# Debugger.net
KiCad netlist of a schematic drawn in Altium Designer
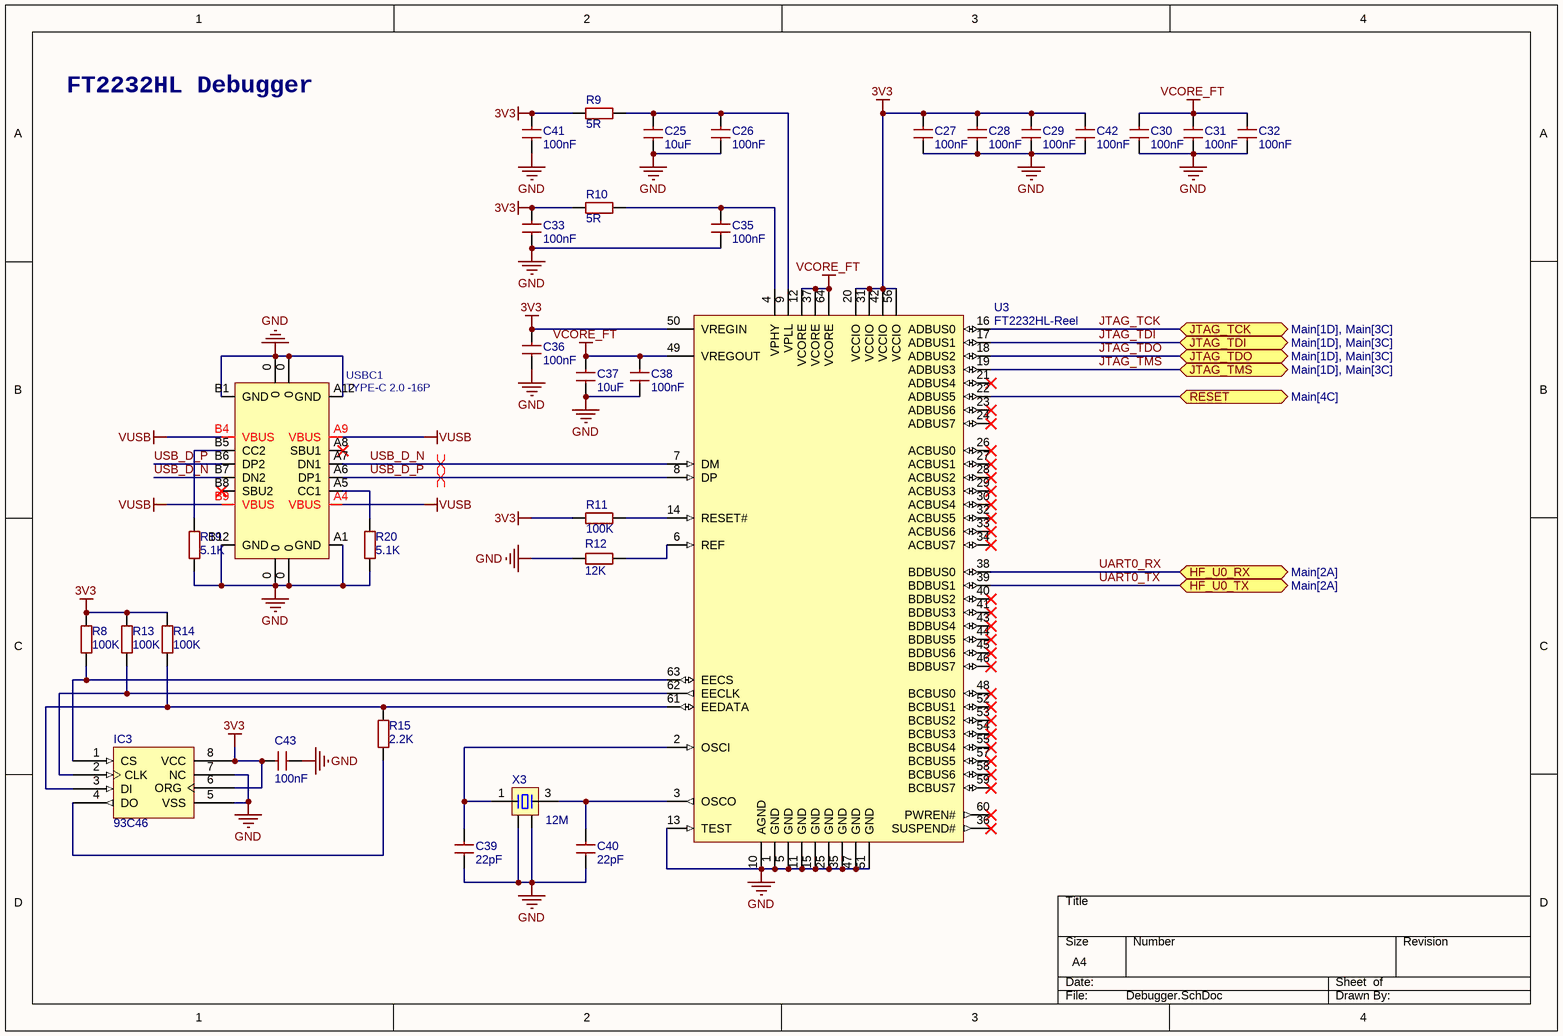
[diagram p0: Debugger.SchDoc]

(export (version "E")
  (design (tool "Eeschema 10.0.6"))
  (components
    (comp (ref "C25")
      (value "10uF")
      (footprint "C0603_NS")
      (description "贴片电容/MLCC电容")
      (libsource (lib "0.1 - 电阻-电容-电感-晶振-晶体-磁珠-电位器-法拉电容-馈通电容") (part "C"))
    )
    (comp (ref "C26")
      (value "100nF")
      (footprint "C0603_NS")
      (description "贴片电容/MLCC电容")
      (libsource (lib "0.1 - 电阻-电容-电感-晶振-晶体-磁珠-电位器-法拉电容-馈通电容") (part "C"))
    )
    (comp (ref "C27")
      (value "100nF")
      (footprint "C0603_NS")
      (description "贴片电容/MLCC电容")
      (libsource (lib "0.1 - 电阻-电容-电感-晶振-晶体-磁珠-电位器-法拉电容-馈通电容") (part "C"))
    )
    (comp (ref "C28")
      (value "100nF")
      (footprint "C0603_NS")
      (description "贴片电容/MLCC电容")
      (libsource (lib "0.1 - 电阻-电容-电感-晶振-晶体-磁珠-电位器-法拉电容-馈通电容") (part "C"))
    )
    (comp (ref "C29")
      (value "100nF")
      (footprint "C0603_NS")
      (description "贴片电容/MLCC电容")
      (libsource (lib "0.1 - 电阻-电容-电感-晶振-晶体-磁珠-电位器-法拉电容-馈通电容") (part "C"))
    )
    (comp (ref "C30")
      (value "100nF")
      (footprint "C0603_NS")
      (description "贴片电容/MLCC电容")
      (libsource (lib "0.1 - 电阻-电容-电感-晶振-晶体-磁珠-电位器-法拉电容-馈通电容") (part "C"))
    )
    (comp (ref "C31")
      (value "100nF")
      (footprint "C0603_NS")
      (description "贴片电容/MLCC电容")
      (libsource (lib "0.1 - 电阻-电容-电感-晶振-晶体-磁珠-电位器-法拉电容-馈通电容") (part "C"))
    )
    (comp (ref "C32")
      (value "100nF")
      (footprint "C0603_NS")
      (description "贴片电容/MLCC电容")
      (libsource (lib "0.1 - 电阻-电容-电感-晶振-晶体-磁珠-电位器-法拉电容-馈通电容") (part "C"))
    )
    (comp (ref "C33")
      (value "100nF")
      (footprint "C0603_NS")
      (description "贴片电容/MLCC电容")
      (libsource (lib "0.1 - 电阻-电容-电感-晶振-晶体-磁珠-电位器-法拉电容-馈通电容") (part "C"))
    )
    (comp (ref "C35")
      (value "100nF")
      (footprint "C0603_NS")
      (description "贴片电容/MLCC电容")
      (libsource (lib "0.1 - 电阻-电容-电感-晶振-晶体-磁珠-电位器-法拉电容-馈通电容") (part "C"))
    )
    (comp (ref "C36")
      (value "100nF")
      (footprint "C0603_NS")
      (description "贴片电容/MLCC电容")
      (libsource (lib "0.1 - 电阻-电容-电感-晶振-晶体-磁珠-电位器-法拉电容-馈通电容") (part "C"))
    )
    (comp (ref "C37")
      (value "10uF")
      (footprint "C0603_NS")
      (description "贴片电容/MLCC电容")
      (libsource (lib "0.1 - 电阻-电容-电感-晶振-晶体-磁珠-电位器-法拉电容-馈通电容") (part "C"))
    )
    (comp (ref "C38")
      (value "100nF")
      (footprint "C0603_NS")
      (description "贴片电容/MLCC电容")
      (libsource (lib "0.1 - 电阻-电容-电感-晶振-晶体-磁珠-电位器-法拉电容-馈通电容") (part "C"))
    )
    (comp (ref "C39")
      (value "22pF")
      (footprint "C0603_NS")
      (description "贴片电容/MLCC电容")
      (libsource (lib "0.1 - 电阻-电容-电感-晶振-晶体-磁珠-电位器-法拉电容-馈通电容") (part "C"))
    )
    (comp (ref "C40")
      (value "22pF")
      (footprint "C0603_NS")
      (description "贴片电容/MLCC电容")
      (libsource (lib "0.1 - 电阻-电容-电感-晶振-晶体-磁珠-电位器-法拉电容-馈通电容") (part "C"))
    )
    (comp (ref "C41")
      (value "100nF")
      (footprint "C0603_NS")
      (description "贴片电容/MLCC电容")
      (libsource (lib "0.1 - 电阻-电容-电感-晶振-晶体-磁珠-电位器-法拉电容-馈通电容") (part "C"))
    )
    (comp (ref "C42")
      (value "100nF")
      (footprint "C0603_NS")
      (description "贴片电容/MLCC电容")
      (libsource (lib "0.1 - 电阻-电容-电感-晶振-晶体-磁珠-电位器-法拉电容-馈通电容") (part "C"))
    )
    (comp (ref "C43")
      (value "100nF")
      (footprint "C0603_NS")
      (description "贴片电容/MLCC电容")
      (libsource (lib "0.1 - 电阻-电容-电感-晶振-晶体-磁珠-电位器-法拉电容-馈通电容") (part "C"))
    )
    (comp (ref "IC3")
      (value "93C46")
      (footprint "SOP8_L")
      (description "外置EEPROM")
      (libsource (lib "0.8 - 常见芯片") (part "93C46"))
    )
    (comp (ref "R8")
      (value "100K")
      (footprint "R0603_NS")
      (description "贴片电阻")
      (libsource (lib "0.1 - 电阻-电容-电感-晶振-晶体-磁珠-电位器-法拉电容-馈通电容") (part "R"))
    )
    (comp (ref "R9")
      (value "5R")
      (footprint "R0603_NS")
      (description "贴片电阻")
      (libsource (lib "") (part "R_2"))
    )
    (comp (ref "R10")
      (value "5R")
      (footprint "R0603_NS")
      (description "贴片电阻")
      (libsource (lib "") (part "R_2"))
    )
    (comp (ref "R11")
      (value "100K")
      (footprint "R0603_NS")
      (description "贴片电阻")
      (libsource (lib "") (part "R_2"))
    )
    (comp (ref "R12")
      (value "12K")
      (footprint "R0603_NS")
      (description "贴片电阻")
      (libsource (lib "") (part "R_3"))
    )
    (comp (ref "R13")
      (value "100K")
      (footprint "R0603_NS")
      (description "贴片电阻")
      (libsource (lib "0.1 - 电阻-电容-电感-晶振-晶体-磁珠-电位器-法拉电容-馈通电容") (part "R"))
    )
    (comp (ref "R14")
      (value "100K")
      (footprint "R0603_NS")
      (description "贴片电阻")
      (libsource (lib "0.1 - 电阻-电容-电感-晶振-晶体-磁珠-电位器-法拉电容-馈通电容") (part "R"))
    )
    (comp (ref "R15")
      (value "2.2K")
      (footprint "R0603_NS")
      (description "贴片电阻")
      (libsource (lib "") (part "R_1"))
    )
    (comp (ref "R19")
      (value "5.1K")
      (footprint "R0603_NS")
      (description "贴片电阻")
      (libsource (lib "0.1 - 电阻-电容-电感-晶振-晶体-磁珠-电位器-法拉电容-馈通电容") (part "R"))
    )
    (comp (ref "R20")
      (value "5.1K")
      (footprint "R0603_NS")
      (description "贴片电阻")
      (libsource (lib "0.1 - 电阻-电容-电感-晶振-晶体-磁珠-电位器-法拉电容-馈通电容") (part "R"))
    )
    (comp (ref "U3")
      (value "FT2232HL-Reel")
      (footprint "LQFP-64_M")
      (description "Dual High Speed USB To Multipurpose UART/FIFO IC, 64-pin LQFP, Tape and Reel")
      (fields (field (name "MANUFACTURER") "FTDI"))
      (libsource (lib "Altium Content Vault") (part "COM-UART-FT2232H-LQFP64"))
    )
    (comp (ref "USBC1")
      (value "TYPE-C 2.0 -16P")
      (footprint "USB-C-SMD_16P")
      (description "USB2.0_Type-C_16Pin母座")
      (libsource (lib "0.6 - 电源_RJ45以太网_音频_SD-TF_SIM_ USB Type-C_HDMI插座") (part "USB2.0_Type-C_16Pin"))
    )
    (comp (ref "X3")
      (value "12M")
      (footprint "XTAL-2025-4P")
      (description "4脚无源晶振(谐振器）")
      (libsource (lib "0.1 - 电阻-电容-电感-晶振-晶体-磁珠-电位器-法拉电容-馈通电容") (part "XTAL-4P"))
    )
  )
  (nets
    (net (code "1") (name "/JTAG_TCK") (class "Default")
      (node (ref "U3") (pin "16") (pinfunction "ADBUS0_16") (pintype "bidirectional"))
    )
    (net (code "2") (name "/JTAG_TDI") (class "Default")
      (node (ref "U3") (pin "17") (pinfunction "ADBUS1_17") (pintype "bidirectional"))
    )
    (net (code "3") (name "/JTAG_TDO") (class "Default")
      (node (ref "U3") (pin "18") (pinfunction "ADBUS2_18") (pintype "bidirectional"))
    )
    (net (code "4") (name "/JTAG_TMS") (class "Default")
      (node (ref "U3") (pin "19") (pinfunction "ADBUS3_19") (pintype "bidirectional"))
    )
    (net (code "5") (name "/RESET") (class "Default")
      (node (ref "U3") (pin "22") (pinfunction "ADBUS5_22") (pintype "bidirectional"))
    )
    (net (code "6") (name "/UART0_RX") (class "Default")
      (node (ref "U3") (pin "38") (pinfunction "BDBUS0_38") (pintype "bidirectional"))
    )
    (net (code "7") (name "/UART0_TX") (class "Default")
      (node (ref "U3") (pin "39") (pinfunction "BDBUS1_39") (pintype "bidirectional"))
    )
    (net (code "8") (name "/USB_D_N") (class "Default")
      (node (ref "U3") (pin "7") (pinfunction "DM_7") (pintype "input"))
      (node (ref "USBC1") (pin "A7") (pinfunction "DN1_A7") (pintype "passive"))
      (node (ref "USBC1") (pin "B7") (pinfunction "DN2_B7") (pintype "passive"))
    )
    (net (code "9") (name "/USB_D_P") (class "Default")
      (node (ref "U3") (pin "8") (pinfunction "DP_8") (pintype "input"))
      (node (ref "USBC1") (pin "A6") (pinfunction "DP1_A6") (pintype "passive"))
      (node (ref "USBC1") (pin "B6") (pinfunction "DP2_B6") (pintype "passive"))
    )
    (net (code "10") (name "3V3") (class "Default")
      (node (ref "C27") (pin "2") (pinfunction "2_2") (pintype "passive"))
      (node (ref "C28") (pin "2") (pinfunction "2_2") (pintype "passive"))
      (node (ref "C29") (pin "2") (pinfunction "2_2") (pintype "passive"))
      (node (ref "C33") (pin "2") (pinfunction "2_2") (pintype "passive"))
      (node (ref "C36") (pin "2") (pinfunction "2_2") (pintype "passive"))
      (node (ref "C41") (pin "2") (pinfunction "2_2") (pintype "passive"))
      (node (ref "C42") (pin "2") (pinfunction "2_2") (pintype "passive"))
      (node (ref "C43") (pin "1") (pinfunction "1_1") (pintype "passive"))
      (node (ref "IC3") (pin "6") (pinfunction "ORG_6") (pintype "passive"))
      (node (ref "IC3") (pin "8") (pinfunction "VCC_8") (pintype "power_in"))
      (node (ref "R10") (pin "2") (pinfunction "2_2") (pintype "passive"))
      (node (ref "R11") (pin "2") (pinfunction "2_2") (pintype "passive"))
      (node (ref "R13") (pin "2") (pinfunction "2_2") (pintype "passive"))
      (node (ref "R14") (pin "2") (pinfunction "2_2") (pintype "passive"))
      (node (ref "R8") (pin "2") (pinfunction "2_2") (pintype "passive"))
      (node (ref "R9") (pin "2") (pinfunction "2_2") (pintype "passive"))
      (node (ref "U3") (pin "20") (pinfunction "VCCIO_20") (pintype "power_in"))
      (node (ref "U3") (pin "31") (pinfunction "VCCIO_31") (pintype "power_in"))
      (node (ref "U3") (pin "42") (pinfunction "VCCIO_42") (pintype "power_in"))
      (node (ref "U3") (pin "50") (pinfunction "VREGIN_50") (pintype "power_in"))
      (node (ref "U3") (pin "56") (pinfunction "VCCIO_56") (pintype "power_in"))
    )
    (net (code "11") (name "GND") (class "Default")
      (node (ref "C25") (pin "1") (pinfunction "1_1") (pintype "passive"))
      (node (ref "C26") (pin "1") (pinfunction "1_1") (pintype "passive"))
      (node (ref "C27") (pin "1") (pinfunction "1_1") (pintype "passive"))
      (node (ref "C28") (pin "1") (pinfunction "1_1") (pintype "passive"))
      (node (ref "C29") (pin "1") (pinfunction "1_1") (pintype "passive"))
      (node (ref "C30") (pin "1") (pinfunction "1_1") (pintype "passive"))
      (node (ref "C31") (pin "1") (pinfunction "1_1") (pintype "passive"))
      (node (ref "C32") (pin "1") (pinfunction "1_1") (pintype "passive"))
      (node (ref "C33") (pin "1") (pinfunction "1_1") (pintype "passive"))
      (node (ref "C35") (pin "1") (pinfunction "1_1") (pintype "passive"))
      (node (ref "C36") (pin "1") (pinfunction "1_1") (pintype "passive"))
      (node (ref "C37") (pin "1") (pinfunction "1_1") (pintype "passive"))
      (node (ref "C38") (pin "1") (pinfunction "1_1") (pintype "passive"))
      (node (ref "C39") (pin "1") (pinfunction "1_1") (pintype "passive"))
      (node (ref "C40") (pin "1") (pinfunction "1_1") (pintype "passive"))
      (node (ref "C41") (pin "1") (pinfunction "1_1") (pintype "passive"))
      (node (ref "C42") (pin "1") (pinfunction "1_1") (pintype "passive"))
      (node (ref "C43") (pin "2") (pinfunction "2_2") (pintype "passive"))
      (node (ref "IC3") (pin "5") (pinfunction "VSS_5") (pintype "passive"))
      (node (ref "IC3") (pin "7") (pinfunction "NC_7") (pintype "passive"))
      (node (ref "R12") (pin "1") (pinfunction "1_1") (pintype "passive"))
      (node (ref "R19") (pin "1") (pinfunction "1_1") (pintype "passive"))
      (node (ref "R20") (pin "1") (pinfunction "1_1") (pintype "passive"))
      (node (ref "U3") (pin "1") (pinfunction "GND_1") (pintype "power_in"))
      (node (ref "U3") (pin "10") (pinfunction "AGND_10") (pintype "power_in"))
      (node (ref "U3") (pin "11") (pinfunction "GND_11") (pintype "power_in"))
      (node (ref "U3") (pin "13") (pinfunction "TEST_13") (pintype "input"))
      (node (ref "U3") (pin "15") (pinfunction "GND_15") (pintype "power_in"))
      (node (ref "U3") (pin "25") (pinfunction "GND_25") (pintype "power_in"))
      (node (ref "U3") (pin "35") (pinfunction "GND_35") (pintype "power_in"))
      (node (ref "U3") (pin "47") (pinfunction "GND_47") (pintype "power_in"))
      (node (ref "U3") (pin "5") (pinfunction "GND_5") (pintype "power_in"))
      (node (ref "U3") (pin "51") (pinfunction "GND_51") (pintype "power_in"))
      (node (ref "USBC1") (pin "0") (pinfunction "0_0") (pintype "passive"))
      (node (ref "USBC1") (pin "A1") (pinfunction "GND_A1") (pintype "passive"))
      (node (ref "USBC1") (pin "A12") (pinfunction "GND_A12") (pintype "passive"))
      (node (ref "USBC1") (pin "B1") (pinfunction "GND_B1") (pintype "passive"))
      (node (ref "USBC1") (pin "B12") (pinfunction "GND_B12") (pintype "passive"))
      (node (ref "X3") (pin "2") (pinfunction "2_2") (pintype "passive"))
      (node (ref "X3") (pin "4") (pinfunction "4_4") (pintype "passive"))
    )
    (net (code "12") (name "Net-(IC3-CLK)") (class "Default")
      (node (ref "IC3") (pin "2") (pinfunction "CLK_2") (pintype "input"))
      (node (ref "R13") (pin "1") (pinfunction "1_1") (pintype "passive"))
      (node (ref "U3") (pin "62") (pinfunction "EECLK_62") (pintype "output"))
    )
    (net (code "13") (name "Net-(IC3-CS)") (class "Default")
      (node (ref "IC3") (pin "1") (pinfunction "CS_1") (pintype "input"))
      (node (ref "R8") (pin "1") (pinfunction "1_1") (pintype "passive"))
      (node (ref "U3") (pin "63") (pinfunction "EECS_63") (pintype "bidirectional"))
    )
    (net (code "14") (name "Net-(IC3-DI)") (class "Default")
      (node (ref "IC3") (pin "3") (pinfunction "DI_3") (pintype "input"))
      (node (ref "R14") (pin "1") (pinfunction "1_1") (pintype "passive"))
      (node (ref "R15") (pin "1") (pinfunction "1_1") (pintype "passive"))
      (node (ref "U3") (pin "61") (pinfunction "EEDATA_61") (pintype "bidirectional"))
    )
    (net (code "15") (name "Net-(IC3-DO)") (class "Default")
      (node (ref "IC3") (pin "4") (pinfunction "DO_4") (pintype "output"))
      (node (ref "R15") (pin "2") (pinfunction "2_2") (pintype "passive"))
    )
    (net (code "16") (name "Net-(U3-OSCI)") (class "Default")
      (node (ref "C39") (pin "2") (pinfunction "2_2") (pintype "passive"))
      (node (ref "U3") (pin "2") (pinfunction "OSCI_2") (pintype "input"))
      (node (ref "X3") (pin "1") (pinfunction "1_1") (pintype "passive"))
    )
    (net (code "17") (name "Net-(U3-OSCO)") (class "Default")
      (node (ref "C40") (pin "2") (pinfunction "2_2") (pintype "passive"))
      (node (ref "U3") (pin "3") (pinfunction "OSCO_3") (pintype "output"))
      (node (ref "X3") (pin "3") (pinfunction "3_3") (pintype "passive"))
    )
    (net (code "18") (name "Net-(U3-REF)") (class "Default")
      (node (ref "R12") (pin "2") (pinfunction "2_2") (pintype "passive"))
      (node (ref "U3") (pin "6") (pinfunction "REF_6") (pintype "input"))
    )
    (net (code "19") (name "Net-(U3-RESET#)") (class "Default")
      (node (ref "R11") (pin "1") (pinfunction "1_1") (pintype "passive"))
      (node (ref "U3") (pin "14") (pinfunction "RESET#_14") (pintype "input"))
    )
    (net (code "20") (name "Net-(U3-VPHY)") (class "Default")
      (node (ref "C35") (pin "2") (pinfunction "2_2") (pintype "passive"))
      (node (ref "R10") (pin "1") (pinfunction "1_1") (pintype "passive"))
      (node (ref "U3") (pin "4") (pinfunction "VPHY_4") (pintype "power_in"))
    )
    (net (code "21") (name "Net-(U3-VPLL)") (class "Default")
      (node (ref "C25") (pin "2") (pinfunction "2_2") (pintype "passive"))
      (node (ref "C26") (pin "2") (pinfunction "2_2") (pintype "passive"))
      (node (ref "R9") (pin "1") (pinfunction "1_1") (pintype "passive"))
      (node (ref "U3") (pin "9") (pinfunction "VPLL_9") (pintype "power_in"))
    )
    (net (code "22") (name "Net-(USBC1-CC1)") (class "Default")
      (node (ref "R20") (pin "2") (pinfunction "2_2") (pintype "passive"))
      (node (ref "USBC1") (pin "A5") (pinfunction "CC1_A5") (pintype "passive"))
    )
    (net (code "23") (name "Net-(USBC1-CC2)") (class "Default")
      (node (ref "R19") (pin "2") (pinfunction "2_2") (pintype "passive"))
      (node (ref "USBC1") (pin "B5") (pinfunction "CC2_B5") (pintype "passive"))
    )
    (net (code "24") (name "VCORE_FT") (class "Default")
      (node (ref "C30") (pin "2") (pinfunction "2_2") (pintype "passive"))
      (node (ref "C31") (pin "2") (pinfunction "2_2") (pintype "passive"))
      (node (ref "C32") (pin "2") (pinfunction "2_2") (pintype "passive"))
      (node (ref "C37") (pin "2") (pinfunction "2_2") (pintype "passive"))
      (node (ref "C38") (pin "2") (pinfunction "2_2") (pintype "passive"))
      (node (ref "U3") (pin "12") (pinfunction "VCORE_12") (pintype "power_in"))
      (node (ref "U3") (pin "37") (pinfunction "VCORE_37") (pintype "power_in"))
      (node (ref "U3") (pin "49") (pinfunction "VREGOUT_49") (pintype "power_in"))
      (node (ref "U3") (pin "64") (pinfunction "VCORE_64") (pintype "power_in"))
    )
    (net (code "25") (name "VUSB") (class "Default")
      (node (ref "USBC1") (pin "A4") (pinfunction "VBUS_A4") (pintype "passive"))
      (node (ref "USBC1") (pin "A9") (pinfunction "VBUS_A9") (pintype "passive"))
      (node (ref "USBC1") (pin "B4") (pinfunction "VBUS_B4") (pintype "passive"))
      (node (ref "USBC1") (pin "B9") (pinfunction "VBUS_B9") (pintype "passive"))
    )
    (net (code "26") (name "unconnected-(U3-ACBUS0-Pad26)") (class "Default")
      (node (ref "U3") (pin "26") (pinfunction "ACBUS0_26") (pintype "bidirectional+no_connect"))
    )
    (net (code "27") (name "unconnected-(U3-ACBUS1-Pad27)") (class "Default")
      (node (ref "U3") (pin "27") (pinfunction "ACBUS1_27") (pintype "bidirectional+no_connect"))
    )
    (net (code "28") (name "unconnected-(U3-ACBUS2-Pad28)") (class "Default")
      (node (ref "U3") (pin "28") (pinfunction "ACBUS2_28") (pintype "bidirectional+no_connect"))
    )
    (net (code "29") (name "unconnected-(U3-ACBUS3-Pad29)") (class "Default")
      (node (ref "U3") (pin "29") (pinfunction "ACBUS3_29") (pintype "bidirectional+no_connect"))
    )
    (net (code "30") (name "unconnected-(U3-ACBUS4-Pad30)") (class "Default")
      (node (ref "U3") (pin "30") (pinfunction "ACBUS4_30") (pintype "bidirectional+no_connect"))
    )
    (net (code "31") (name "unconnected-(U3-ACBUS5-Pad32)") (class "Default")
      (node (ref "U3") (pin "32") (pinfunction "ACBUS5_32") (pintype "bidirectional+no_connect"))
    )
    (net (code "32") (name "unconnected-(U3-ACBUS6-Pad33)") (class "Default")
      (node (ref "U3") (pin "33") (pinfunction "ACBUS6_33") (pintype "bidirectional+no_connect"))
    )
    (net (code "33") (name "unconnected-(U3-ACBUS7-Pad34)") (class "Default")
      (node (ref "U3") (pin "34") (pinfunction "ACBUS7_34") (pintype "bidirectional+no_connect"))
    )
    (net (code "34") (name "unconnected-(U3-ADBUS4-Pad21)") (class "Default")
      (node (ref "U3") (pin "21") (pinfunction "ADBUS4_21") (pintype "bidirectional+no_connect"))
    )
    (net (code "35") (name "unconnected-(U3-ADBUS6-Pad23)") (class "Default")
      (node (ref "U3") (pin "23") (pinfunction "ADBUS6_23") (pintype "bidirectional+no_connect"))
    )
    (net (code "36") (name "unconnected-(U3-ADBUS7-Pad24)") (class "Default")
      (node (ref "U3") (pin "24") (pinfunction "ADBUS7_24") (pintype "bidirectional+no_connect"))
    )
    (net (code "37") (name "unconnected-(U3-BCBUS0-Pad48)") (class "Default")
      (node (ref "U3") (pin "48") (pinfunction "BCBUS0_48") (pintype "bidirectional+no_connect"))
    )
    (net (code "38") (name "unconnected-(U3-BCBUS1-Pad52)") (class "Default")
      (node (ref "U3") (pin "52") (pinfunction "BCBUS1_52") (pintype "bidirectional+no_connect"))
    )
    (net (code "39") (name "unconnected-(U3-BCBUS2-Pad53)") (class "Default")
      (node (ref "U3") (pin "53") (pinfunction "BCBUS2_53") (pintype "bidirectional+no_connect"))
    )
    (net (code "40") (name "unconnected-(U3-BCBUS3-Pad54)") (class "Default")
      (node (ref "U3") (pin "54") (pinfunction "BCBUS3_54") (pintype "bidirectional+no_connect"))
    )
    (net (code "41") (name "unconnected-(U3-BCBUS4-Pad55)") (class "Default")
      (node (ref "U3") (pin "55") (pinfunction "BCBUS4_55") (pintype "bidirectional+no_connect"))
    )
    (net (code "42") (name "unconnected-(U3-BCBUS5-Pad57)") (class "Default")
      (node (ref "U3") (pin "57") (pinfunction "BCBUS5_57") (pintype "bidirectional+no_connect"))
    )
    (net (code "43") (name "unconnected-(U3-BCBUS6-Pad58)") (class "Default")
      (node (ref "U3") (pin "58") (pinfunction "BCBUS6_58") (pintype "bidirectional+no_connect"))
    )
    (net (code "44") (name "unconnected-(U3-BCBUS7-Pad59)") (class "Default")
      (node (ref "U3") (pin "59") (pinfunction "BCBUS7_59") (pintype "bidirectional+no_connect"))
    )
    (net (code "45") (name "unconnected-(U3-BDBUS2-Pad40)") (class "Default")
      (node (ref "U3") (pin "40") (pinfunction "BDBUS2_40") (pintype "bidirectional+no_connect"))
    )
    (net (code "46") (name "unconnected-(U3-BDBUS3-Pad41)") (class "Default")
      (node (ref "U3") (pin "41") (pinfunction "BDBUS3_41") (pintype "bidirectional+no_connect"))
    )
    (net (code "47") (name "unconnected-(U3-BDBUS4-Pad43)") (class "Default")
      (node (ref "U3") (pin "43") (pinfunction "BDBUS4_43") (pintype "bidirectional+no_connect"))
    )
    (net (code "48") (name "unconnected-(U3-BDBUS5-Pad44)") (class "Default")
      (node (ref "U3") (pin "44") (pinfunction "BDBUS5_44") (pintype "bidirectional+no_connect"))
    )
    (net (code "49") (name "unconnected-(U3-BDBUS6-Pad45)") (class "Default")
      (node (ref "U3") (pin "45") (pinfunction "BDBUS6_45") (pintype "bidirectional+no_connect"))
    )
    (net (code "50") (name "unconnected-(U3-BDBUS7-Pad46)") (class "Default")
      (node (ref "U3") (pin "46") (pinfunction "BDBUS7_46") (pintype "bidirectional+no_connect"))
    )
    (net (code "51") (name "unconnected-(U3-PWREN#-Pad60)") (class "Default")
      (node (ref "U3") (pin "60") (pinfunction "PWREN#_60") (pintype "output+no_connect"))
    )
    (net (code "52") (name "unconnected-(U3-SUSPEND#-Pad36)") (class "Default")
      (node (ref "U3") (pin "36") (pinfunction "SUSPEND#_36") (pintype "output+no_connect"))
    )
    (net (code "53") (name "unconnected-(USBC1-SBU1-PadA8)") (class "Default")
      (node (ref "USBC1") (pin "A8") (pinfunction "SBU1_A8") (pintype "passive+no_connect"))
    )
    (net (code "54") (name "unconnected-(USBC1-SBU2-PadB8)") (class "Default")
      (node (ref "USBC1") (pin "B8") (pinfunction "SBU2_B8") (pintype "passive+no_connect"))
    )
  )
)
